# ObjPoint01-00.net
KiCad netlist of a schematic drawn in Altium Designer
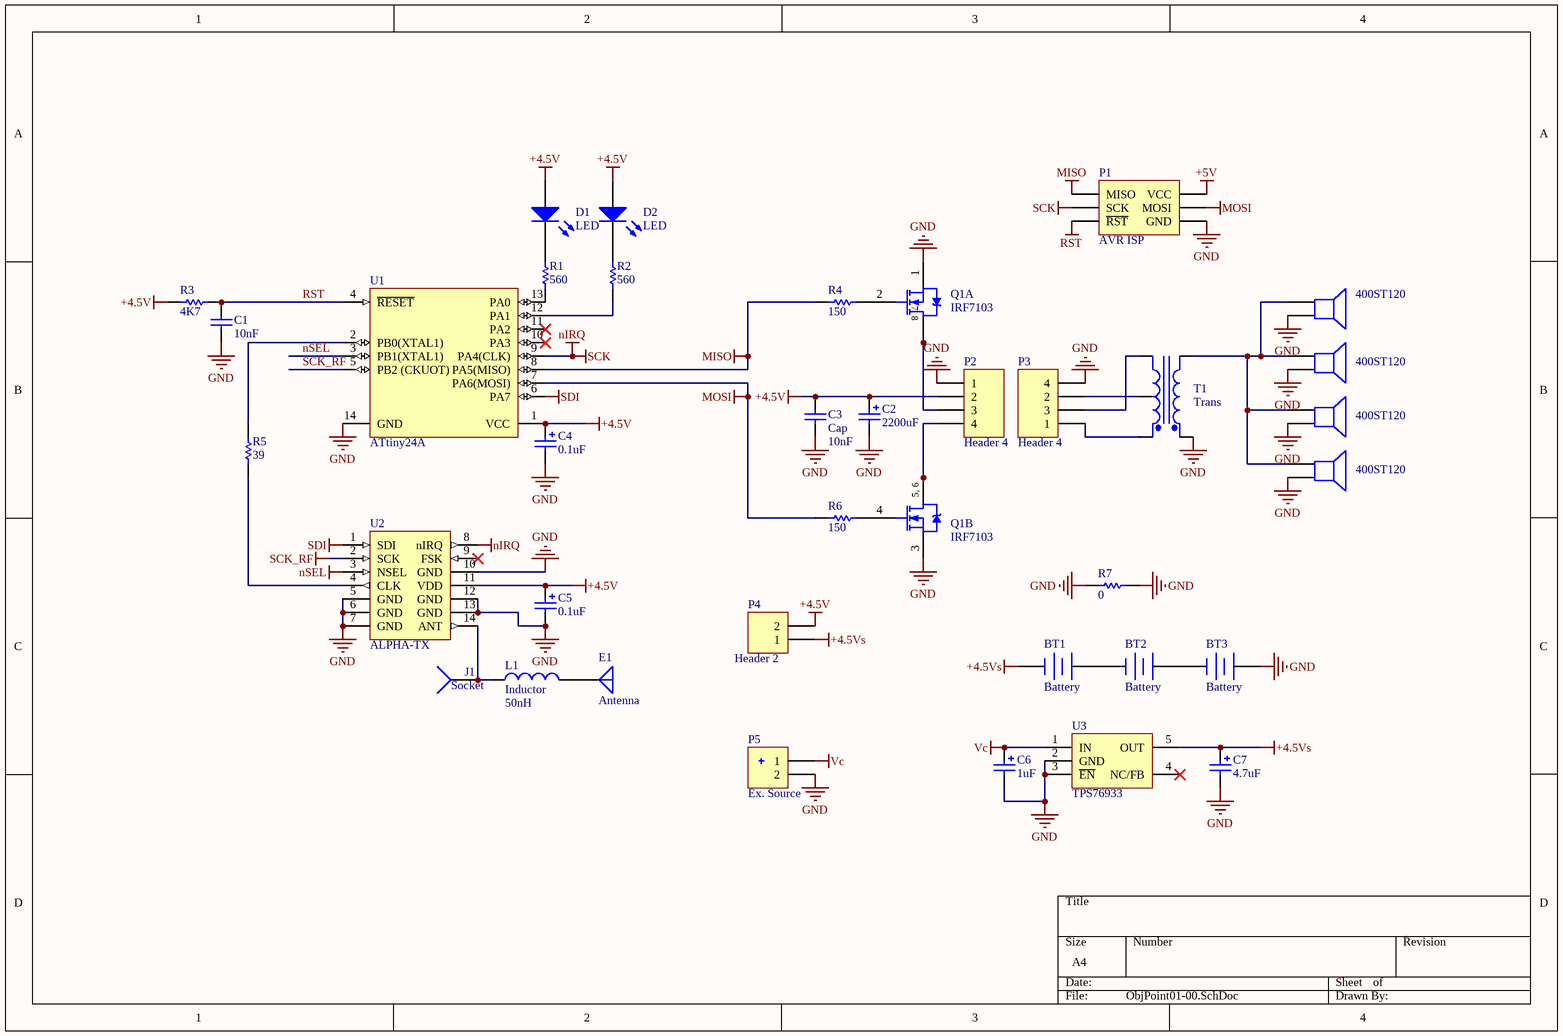
[diagram p0: ObjPoint01-00.SchDoc]

(export (version "E")
  (design (tool "Eeschema 10.0.6"))
  (components
    (comp (ref "BT1")
      (value "Battery")
      (footprint "AAA Battery Holder")
      (description "Multicell Battery")
      (libsource (lib "Miscellaneous Devices") (part "Battery"))
    )
    (comp (ref "BT2")
      (value "Battery")
      (footprint "AAA Battery Holder")
      (description "Multicell Battery")
      (libsource (lib "Miscellaneous Devices") (part "Battery"))
    )
    (comp (ref "BT3")
      (value "Battery")
      (footprint "AAA Battery Holder")
      (description "Multicell Battery")
      (libsource (lib "Miscellaneous Devices") (part "Battery"))
    )
    (comp (ref "C1")
      (value "10nF")
      (footprint "1206")
      (description "Capacitor (Semiconductor SIM Model)")
      (fields (field (name "Comment") "SMD Capacitor") (field (name "PUBLISHER") "Altium Limited"))
      (libsource (lib "Arthur Shematic") (part "SMD Capacitor"))
    )
    (comp (ref "C2")
      (value "2200uF")
      (footprint "Capasitor 13.3mm diametras 20.3 aukstis tarp koju 5mm kojos storis 0.6mm")
      (description "Capacitor (Semiconductor SIM Model)")
      (fields (field (name "Comment") "Cap") (field (name "PUBLISHER") "Altium Limited"))
      (libsource (lib "") (part "Tantalum SMD Capacitors_1"))
    )
    (comp (ref "C3")
      (value "Cap")
      (footprint "0805")
      (description "Capacitor")
      (fields (field (name "ALTIUM_VALUE") "10nF") (field (name "PUBLISHER") "Altium Limited"))
      (libsource (lib "Miscellaneous Devices") (part "Cap"))
    )
    (comp (ref "C4")
      (value "0.1uF")
      (footprint "A")
      (description "Capacitor (Semiconductor SIM Model)")
      (fields (field (name "Comment") "Tantalum SMD Capacitors") (field (name "PUBLISHER") "Altium Limited"))
      (libsource (lib "Arthur Shematic") (part "Tantalum SMD Capacitors"))
    )
    (comp (ref "C5")
      (value "0.1uF")
      (footprint "A")
      (description "Capacitor (Semiconductor SIM Model)")
      (fields (field (name "Comment") "Tantalum SMD Capacitors") (field (name "PUBLISHER") "Altium Limited"))
      (libsource (lib "Arthur Shematic") (part "Tantalum SMD Capacitors"))
    )
    (comp (ref "C6")
      (value "1uF")
      (footprint "A")
      (description "Capacitor (Semiconductor SIM Model)")
      (fields (field (name "Comment") "Tantalum SMD Capacitors") (field (name "PUBLISHER") "Altium Limited"))
      (libsource (lib "Arthur Shematic") (part "Tantalum SMD Capacitors"))
    )
    (comp (ref "C7")
      (value "4.7uF")
      (footprint "A")
      (description "Capacitor (Semiconductor SIM Model)")
      (fields (field (name "Comment") "Tantalum SMD Capacitors") (field (name "PUBLISHER") "Altium Limited"))
      (libsource (lib "Arthur Shematic") (part "Tantalum SMD Capacitors"))
    )
    (comp (ref "D1")
      (value "LED")
      (footprint "LED 3mm DIP")
      (description "Typical INFRARED GaAs LED")
      (fields (field (name "PUBLISHER") "Altium Limited"))
      (libsource (lib "Miscellaneous Devices") (part "LED0"))
    )
    (comp (ref "D2")
      (value "LED")
      (footprint "LED 3mm DIP")
      (description "Typical INFRARED GaAs LED")
      (fields (field (name "PUBLISHER") "Altium Limited"))
      (libsource (lib "Miscellaneous Devices") (part "LED0"))
    )
    (comp (ref "E1")
      (value "Antenna")
      (description "Generic Antenna")
      (fields (field (name "PUBLISHER") "Altium Limited"))
      (libsource (lib "Miscellaneous Devices") (part "Antenna"))
    )
    (comp (ref "J1")
      (value "Socket")
      (footprint "PIN1")
      (fields (field (name "PUBLISHER") "Altium Limited"))
      (libsource (lib "Miscellaneous Connectors") (part "Socket"))
    )
    (comp (ref "L1")
      (value "Inductor")
      (footprint "INDC2012L")
      (fields (field (name "ALTIUM_VALUE") "50nH") (field (name "PUBLISHER") "Altium Limited"))
      (libsource (lib "Miscellaneous Devices") (part "Inductor"))
    )
    (comp (ref "LS1")
      (value "400ST120")
      (footprint "400ST 120")
      (description "Loudspeaker")
      (fields (field (name "PUBLISHER") "Altium Limited"))
      (libsource (lib "Miscellaneous Devices") (part "Speaker"))
    )
    (comp (ref "LS2")
      (value "400ST120")
      (footprint "400ST 120")
      (description "Loudspeaker")
      (fields (field (name "PUBLISHER") "Altium Limited"))
      (libsource (lib "Miscellaneous Devices") (part "Speaker"))
    )
    (comp (ref "LS3")
      (value "400ST120")
      (footprint "400ST 120")
      (description "Loudspeaker")
      (fields (field (name "PUBLISHER") "Altium Limited"))
      (libsource (lib "Miscellaneous Devices") (part "Speaker"))
    )
    (comp (ref "LS4")
      (value "400ST120")
      (footprint "400ST 120")
      (description "Loudspeaker")
      (fields (field (name "PUBLISHER") "Altium Limited"))
      (libsource (lib "Miscellaneous Devices") (part "Speaker"))
    )
    (comp (ref "P1")
      (value "AVR ISP")
      (footprint "HDR2X3")
      (description "Header, 6-Pin")
      (fields (field (name "PUBLISHER") "Altium Limited"))
      (libsource (lib "Arthur Shematic") (part "AVR ISP"))
    )
    (comp (ref "P2")
      (value "Header 4")
      (footprint "HDR1X4")
      (description "Header, 4-Pin")
      (fields (field (name "PUBLISHER") "Altium Limited"))
      (libsource (lib "") (part "Header 4_1"))
    )
    (comp (ref "P3")
      (value "Header 4")
      (footprint "HDR1X4")
      (description "Header, 4-Pin")
      (fields (field (name "PUBLISHER") "Altium Limited"))
      (libsource (lib "Miscellaneous Connectors") (part "Header 4"))
    )
    (comp (ref "P4")
      (value "Header 2")
      (footprint "HDR1X2")
      (description "Header, 2-Pin")
      (fields (field (name "PUBLISHER") "Altium Limited"))
      (libsource (lib "Miscellaneous Connectors") (part "Header 2"))
    )
    (comp (ref "P5")
      (value "Ex. Source")
      (footprint "HDR1X2")
      (description "Header, 2-Pin")
      (fields (field (name "PUBLISHER") "Altium Limited"))
      (libsource (lib "Arthur Shematic") (part "Maitinimas"))
    )
    (comp (ref "Q1")
      (value "IRF7103")
      (footprint "SO-8_N")
      (description "HEXFET Power MOSFET")
      (fields (field (name "PUBLISHER") "Altium Limited"))
      (libsource (lib "IR Discrete MOSFET - Power") (part "IRF7103"))
    )
    (comp (ref "R1")
      (value "560")
      (footprint "0805")
      (description "Semiconductor Resistor")
      (fields (field (name "Comment") "SMD Resistor") (field (name "PUBLISHER") "Altium Limited"))
      (libsource (lib "Arthur Shematic") (part "SMD Resistor"))
    )
    (comp (ref "R2")
      (value "560")
      (footprint "0805")
      (description "Semiconductor Resistor")
      (fields (field (name "Comment") "SMD Resistor") (field (name "PUBLISHER") "Altium Limited"))
      (libsource (lib "Arthur Shematic") (part "SMD Resistor"))
    )
    (comp (ref "R3")
      (value "4K7")
      (footprint "0805")
      (description "Semiconductor Resistor")
      (fields (field (name "Comment") "SMD Resistor") (field (name "PUBLISHER") "Altium Limited"))
      (libsource (lib "Arthur Shematic") (part "SMD Resistor"))
    )
    (comp (ref "R4")
      (value "150")
      (footprint "0805")
      (description "Semiconductor Resistor")
      (fields (field (name "Comment") "SMD Resistor") (field (name "PUBLISHER") "Altium Limited"))
      (libsource (lib "Arthur Shematic") (part "SMD Resistor"))
    )
    (comp (ref "R5")
      (value "39")
      (footprint "0805")
      (description "Semiconductor Resistor")
      (fields (field (name "Comment") "SMD Resistor") (field (name "PUBLISHER") "Altium Limited"))
      (libsource (lib "Arthur Shematic") (part "SMD Resistor"))
    )
    (comp (ref "R6")
      (value "150")
      (footprint "1206")
      (description "Semiconductor Resistor")
      (fields (field (name "Comment") "SMD Resistor") (field (name "PUBLISHER") "Altium Limited"))
      (libsource (lib "Arthur Shematic") (part "SMD Resistor"))
    )
    (comp (ref "R7")
      (value "0")
      (footprint "1206")
      (description "Semiconductor Resistor")
      (fields (field (name "Comment") "SMD Resistor") (field (name "PUBLISHER") "Altium Limited"))
      (libsource (lib "Arthur Shematic") (part "SMD Resistor"))
    )
    (comp (ref "T1")
      (value "Trans")
      (footprint "TRF_5")
      (description "Center-Tapped Transformer (Coupled Inductor Model)")
      (fields (field (name "PUBLISHER") "Altium Limited"))
      (libsource (lib "Miscellaneous Devices") (part "Trans CT"))
    )
    (comp (ref "U1")
      (value "ATtiny24A")
      (footprint "Gennum Footprints:SOIC14T_L")
      (description "ATtiny261A")
      (libsource (lib "Arthur Shematic") (part "ATtiny261A"))
    )
    (comp (ref "U2")
      (value "ALPHA-TX")
      (footprint "ALPHA-TX(RFM02) [SMD]")
      (description "FM Transmitter Module")
      (libsource (lib "Arthur Shematic") (part "ALPHA-TX"))
    )
    (comp (ref "U3")
      (value "TPS76933")
      (footprint "SOT23-5AM")
      (description "ULTRALOW-POWER 100-mA LOW-DROPOUT LINEAR REGULATORS")
      (libsource (lib "Arthur Shematic") (part "TPS769xx"))
    )
  )
  (nets
    (net (code "1") (name "+4.5V") (class "Default")
      (node (ref "C2") (pin "2") (pinfunction "2_2") (pintype "passive"))
      (node (ref "C3") (pin "2") (pinfunction "2_2") (pintype "passive"))
      (node (ref "C4") (pin "1") (pinfunction "1_1") (pintype "passive"))
      (node (ref "C5") (pin "1") (pinfunction "1_1") (pintype "passive"))
      (node (ref "D1") (pin "1") (pinfunction "A_1") (pintype "passive"))
      (node (ref "D2") (pin "1") (pinfunction "A_1") (pintype "passive"))
      (node (ref "P2") (pin "2") (pinfunction "2_2") (pintype "passive"))
      (node (ref "P4") (pin "2") (pinfunction "2_2") (pintype "passive"))
      (node (ref "R3") (pin "1") (pinfunction "1_1") (pintype "passive"))
      (node (ref "U1") (pin "1") (pinfunction "VCC_1") (pintype "power_in"))
      (node (ref "U2") (pin "11") (pinfunction "VDD_11") (pintype "power_in"))
    )
    (net (code "2") (name "+4.5Vs") (class "Default")
      (node (ref "BT1") (pin "2") (pinfunction "-_2") (pintype "passive"))
      (node (ref "C7") (pin "1") (pinfunction "1_1") (pintype "passive"))
      (node (ref "P4") (pin "1") (pinfunction "1_1") (pintype "passive"))
      (node (ref "U3") (pin "5") (pinfunction "OUT_5") (pintype "power_in"))
    )
    (net (code "3") (name "+5V") (class "Default")
      (node (ref "P1") (pin "2") (pinfunction "VCC_2") (pintype "passive"))
    )
    (net (code "4") (name "GND") (class "Default")
      (node (ref "BT3") (pin "1") (pinfunction "+_1") (pintype "passive"))
      (node (ref "C1") (pin "1") (pinfunction "1_1") (pintype "passive"))
      (node (ref "C2") (pin "1") (pinfunction "1_1") (pintype "passive"))
      (node (ref "C3") (pin "1") (pinfunction "1_1") (pintype "passive"))
      (node (ref "C4") (pin "2") (pinfunction "2_2") (pintype "passive"))
      (node (ref "C5") (pin "2") (pinfunction "2_2") (pintype "passive"))
      (node (ref "C6") (pin "2") (pinfunction "2_2") (pintype "passive"))
      (node (ref "C7") (pin "2") (pinfunction "2_2") (pintype "passive"))
      (node (ref "LS1") (pin "2") (pinfunction "2_2") (pintype "passive"))
      (node (ref "LS2") (pin "2") (pinfunction "2_2") (pintype "passive"))
      (node (ref "LS3") (pin "2") (pinfunction "2_2") (pintype "passive"))
      (node (ref "LS4") (pin "2") (pinfunction "2_2") (pintype "passive"))
      (node (ref "P1") (pin "6") (pinfunction "GND_6") (pintype "passive"))
      (node (ref "P2") (pin "1") (pinfunction "1_1") (pintype "passive"))
      (node (ref "P3") (pin "4") (pinfunction "4_4") (pintype "passive"))
      (node (ref "P5") (pin "2") (pinfunction "2_2") (pintype "passive"))
      (node (ref "Q1") (pin "1") (pinfunction "S_1") (pintype "passive"))
      (node (ref "Q1") (pin "3") (pinfunction "S_3") (pintype "passive"))
      (node (ref "R7") (pin "1") (pinfunction "1_1") (pintype "passive"))
      (node (ref "R7") (pin "2") (pinfunction "2_2") (pintype "passive"))
      (node (ref "T1") (pin "1") (pinfunction "Pri+_1") (pintype "passive"))
      (node (ref "U1") (pin "14") (pinfunction "GND_14") (pintype "power_in"))
      (node (ref "U2") (pin "10") (pinfunction "GND_10") (pintype "power_in"))
      (node (ref "U2") (pin "12") (pinfunction "GND_12") (pintype "power_in"))
      (node (ref "U2") (pin "13") (pinfunction "GND_13") (pintype "power_in"))
      (node (ref "U2") (pin "5") (pinfunction "GND_5") (pintype "power_in"))
      (node (ref "U2") (pin "6") (pinfunction "GND_6") (pintype "power_in"))
      (node (ref "U2") (pin "7") (pinfunction "GND_7") (pintype "power_in"))
      (node (ref "U3") (pin "2") (pinfunction "GND_2") (pintype "power_in"))
      (node (ref "U3") (pin "3") (pinfunction "~{EN}_3") (pintype "power_in"))
    )
    (net (code "5") (name "MISO") (class "Default")
      (node (ref "P1") (pin "1") (pinfunction "MISO_1") (pintype "passive"))
      (node (ref "R4") (pin "1") (pinfunction "1_1") (pintype "passive"))
      (node (ref "U1") (pin "8") (pinfunction "PA5(MISO)_8") (pintype "bidirectional"))
    )
    (net (code "6") (name "MOSI") (class "Default")
      (node (ref "P1") (pin "4") (pinfunction "MOSI_4") (pintype "passive"))
      (node (ref "R6") (pin "1") (pinfunction "1_1") (pintype "passive"))
      (node (ref "U1") (pin "7") (pinfunction "PA6(MOSI)_7") (pintype "bidirectional"))
    )
    (net (code "7") (name "Net-(BT1-+)") (class "Default")
      (node (ref "BT1") (pin "1") (pinfunction "+_1") (pintype "passive"))
      (node (ref "BT2") (pin "2") (pinfunction "-_2") (pintype "passive"))
    )
    (net (code "8") (name "Net-(BT2-+)") (class "Default")
      (node (ref "BT2") (pin "1") (pinfunction "+_1") (pintype "passive"))
      (node (ref "BT3") (pin "2") (pinfunction "-_2") (pintype "passive"))
    )
    (net (code "9") (name "Net-(D1-K)") (class "Default")
      (node (ref "D1") (pin "2") (pinfunction "K_2") (pintype "passive"))
      (node (ref "R1") (pin "1") (pinfunction "1_1") (pintype "passive"))
    )
    (net (code "10") (name "Net-(D2-K)") (class "Default")
      (node (ref "D2") (pin "2") (pinfunction "K_2") (pintype "passive"))
      (node (ref "R2") (pin "2") (pinfunction "2_2") (pintype "passive"))
    )
    (net (code "11") (name "Net-(E1-A)") (class "Default")
      (node (ref "E1") (pin "1") (pinfunction "A_1") (pintype "passive"))
      (node (ref "L1") (pin "2") (pinfunction "2_2") (pintype "passive"))
    )
    (net (code "12") (name "Net-(P2-Pad3)") (class "Default")
      (node (ref "P2") (pin "3") (pinfunction "3_3") (pintype "passive"))
      (node (ref "Q1") (pin "7") (pinfunction "D_7") (pintype "passive"))
      (node (ref "Q1") (pin "8") (pinfunction "D_8") (pintype "passive"))
    )
    (net (code "13") (name "Net-(P2-Pad4)") (class "Default")
      (node (ref "P2") (pin "4") (pinfunction "4_4") (pintype "passive"))
      (node (ref "Q1") (pin "5") (pinfunction "D_5") (pintype "passive"))
      (node (ref "Q1") (pin "6") (pinfunction "D_6") (pintype "passive"))
    )
    (net (code "14") (name "Net-(Q1A-G)") (class "Default")
      (node (ref "Q1") (pin "2") (pinfunction "G_2") (pintype "passive"))
      (node (ref "R4") (pin "2") (pinfunction "2_2") (pintype "passive"))
    )
    (net (code "15") (name "Net-(Q1B-G)") (class "Default")
      (node (ref "Q1") (pin "4") (pinfunction "G_4") (pintype "passive"))
      (node (ref "R6") (pin "2") (pinfunction "2_2") (pintype "passive"))
    )
    (net (code "16") (name "Net-(T1-Pri-)") (class "Default")
      (node (ref "LS1") (pin "1") (pinfunction "1_1") (pintype "passive"))
      (node (ref "LS2") (pin "1") (pinfunction "1_1") (pintype "passive"))
      (node (ref "LS3") (pin "1") (pinfunction "1_1") (pintype "passive"))
      (node (ref "LS4") (pin "1") (pinfunction "1_1") (pintype "passive"))
      (node (ref "T1") (pin "2") (pinfunction "Pri-_2") (pintype "passive"))
    )
    (net (code "17") (name "Net-(T1-Sec+)") (class "Default")
      (node (ref "P3") (pin "2") (pinfunction "2_2") (pintype "passive"))
      (node (ref "T1") (pin "3") (pinfunction "Sec+_3") (pintype "passive"))
    )
    (net (code "18") (name "Net-(T1-Sec-)") (class "Default")
      (node (ref "P3") (pin "1") (pinfunction "1_1") (pintype "passive"))
      (node (ref "T1") (pin "5") (pinfunction "Sec-_5") (pintype "passive"))
    )
    (net (code "19") (name "Net-(T1-SecCT)") (class "Default")
      (node (ref "P3") (pin "3") (pinfunction "3_3") (pintype "passive"))
      (node (ref "T1") (pin "4") (pinfunction "SecCT_4") (pintype "passive"))
    )
    (net (code "20") (name "Net-(U1-PA0)") (class "Default")
      (node (ref "R1") (pin "2") (pinfunction "2_2") (pintype "passive"))
      (node (ref "U1") (pin "13") (pinfunction "PA0_13") (pintype "bidirectional"))
    )
    (net (code "21") (name "Net-(U1-PA1)") (class "Default")
      (node (ref "R2") (pin "1") (pinfunction "1_1") (pintype "passive"))
      (node (ref "U1") (pin "12") (pinfunction "PA1_12") (pintype "bidirectional"))
    )
    (net (code "22") (name "Net-(U1-PB0(XTAL1))") (class "Default")
      (node (ref "R5") (pin "2") (pinfunction "2_2") (pintype "passive"))
      (node (ref "U1") (pin "2") (pinfunction "PB0(XTAL1)_2") (pintype "bidirectional"))
    )
    (net (code "23") (name "Net-(U2-ANT)") (class "Default")
      (node (ref "J1") (pin "1") (pinfunction "1_1") (pintype "passive"))
      (node (ref "L1") (pin "1") (pinfunction "1_1") (pintype "passive"))
      (node (ref "U2") (pin "14") (pinfunction "ANT_14") (pintype "output"))
    )
    (net (code "24") (name "Net-(U2-CLK)") (class "Default")
      (node (ref "R5") (pin "1") (pinfunction "1_1") (pintype "passive"))
      (node (ref "U2") (pin "4") (pinfunction "CLK_4") (pintype "output"))
    )
    (net (code "25") (name "RST") (class "Default")
      (node (ref "C1") (pin "2") (pinfunction "2_2") (pintype "passive"))
      (node (ref "P1") (pin "5") (pinfunction "~{RST}_5") (pintype "passive"))
      (node (ref "R3") (pin "2") (pinfunction "2_2") (pintype "passive"))
      (node (ref "U1") (pin "4") (pinfunction "~{RESET}_4") (pintype "input"))
    )
    (net (code "26") (name "SCK") (class "Default")
      (node (ref "P1") (pin "3") (pinfunction "SCK_3") (pintype "passive"))
      (node (ref "U1") (pin "9") (pinfunction "PA4(CLK)_9") (pintype "bidirectional"))
      (node (ref "U2") (pin "8") (pinfunction "nIRQ_8") (pintype "output"))
    )
    (net (code "27") (name "SCK_RF") (class "Default")
      (node (ref "U1") (pin "5") (pinfunction "PB2_(CKUOT)_5") (pintype "bidirectional"))
      (node (ref "U2") (pin "2") (pinfunction "SCK_2") (pintype "input"))
    )
    (net (code "28") (name "SDI") (class "Default")
      (node (ref "U1") (pin "6") (pinfunction "PA7_6") (pintype "bidirectional"))
      (node (ref "U2") (pin "1") (pinfunction "SDI_1") (pintype "input"))
    )
    (net (code "29") (name "Vc") (class "Default")
      (node (ref "C6") (pin "1") (pinfunction "1_1") (pintype "passive"))
      (node (ref "P5") (pin "1") (pinfunction "1_1") (pintype "passive"))
      (node (ref "U3") (pin "1") (pinfunction "IN_1") (pintype "power_in"))
    )
    (net (code "30") (name "nSEL") (class "Default")
      (node (ref "U1") (pin "3") (pinfunction "PB1(XTAL1)_3") (pintype "bidirectional"))
      (node (ref "U2") (pin "3") (pinfunction "NSEL_3") (pintype "input"))
    )
    (net (code "31") (name "unconnected-(U1-PA2-Pad11)") (class "Default")
      (node (ref "U1") (pin "11") (pinfunction "PA2_11") (pintype "bidirectional+no_connect"))
    )
    (net (code "32") (name "unconnected-(U1-PA3-Pad10)") (class "Default")
      (node (ref "U1") (pin "10") (pinfunction "PA3_10") (pintype "bidirectional+no_connect"))
    )
    (net (code "33") (name "unconnected-(U2-FSK-Pad9)") (class "Default")
      (node (ref "U2") (pin "9") (pinfunction "FSK_9") (pintype "input+no_connect"))
    )
    (net (code "34") (name "unconnected-(U3-NC{slash}FB-Pad4)") (class "Default")
      (node (ref "U3") (pin "4") (pinfunction "NC/FB_4") (pintype "power_in+no_connect"))
    )
  )
)
